# 06_-_SAMA7D65-DDR3L.net
KiCad netlist of a schematic drawn in Altium Designer
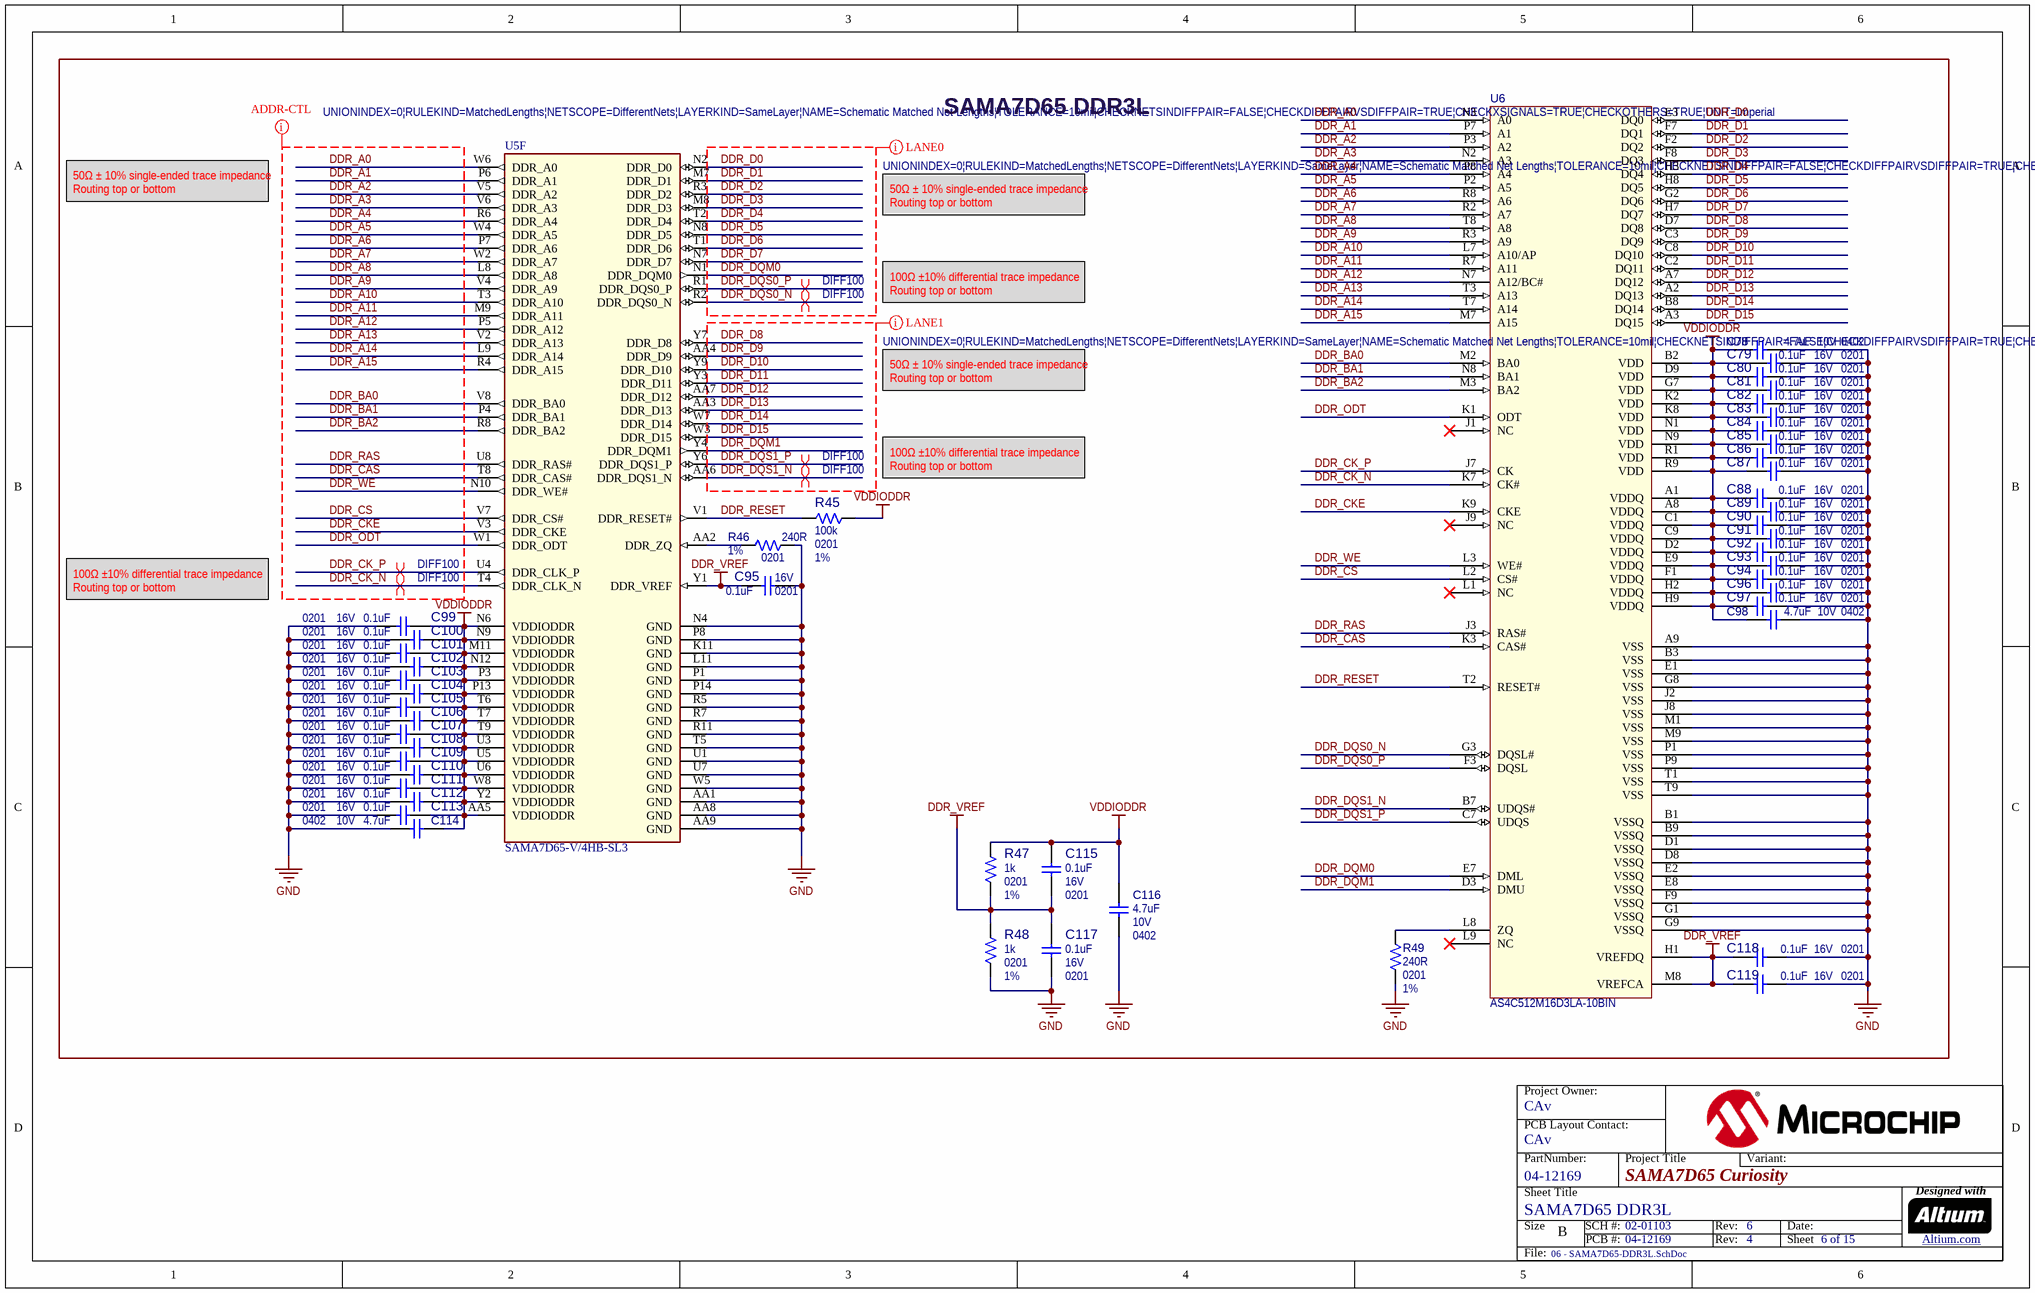
[diagram p0: 06 - SAMA7D65-DDR3L.SchDoc]

(export (version "E")
  (design (tool "Eeschema 10.0.6"))
  (components
    (comp (ref "C78")
      (value "4.7uF")
      (footprint "CAP_C_0402")
      (description "Capacitor")
      (fields
        (field (name "VOLTAGE") "10V")
        (field (name "PACKAGE") "0402")
        (field (name "TOLERANCE") "10%")
        (field (name "Comment") "Capacitor NP")
        (field (name "OWNER") "Jesus Aviles")
      )
      (libsource (lib "MCHP-CDB") (part "Capacitor NP"))
    )
    (comp (ref "C79")
      (value "0.1uF")
      (footprint "CAP_C_0201")
      (fields
        (field (name "VOLTAGE") "16V")
        (field (name "PACKAGE") "0201")
        (field (name "TOLERANCE") "10%")
        (field (name "Comment") "Capacitor NP")
        (field (name "OWNER") "Dragos Danaila")
      )
      (libsource (lib "") (part "Capacitor NP_1"))
    )
    (comp (ref "C80")
      (value "0.1uF")
      (footprint "CAP_C_0201")
      (fields
        (field (name "VOLTAGE") "16V")
        (field (name "PACKAGE") "0201")
        (field (name "TOLERANCE") "10%")
        (field (name "Comment") "Capacitor NP")
        (field (name "OWNER") "Dragos Danaila")
      )
      (libsource (lib "") (part "Capacitor NP_1"))
    )
    (comp (ref "C81")
      (value "0.1uF")
      (footprint "CAP_C_0201")
      (fields
        (field (name "VOLTAGE") "16V")
        (field (name "PACKAGE") "0201")
        (field (name "TOLERANCE") "10%")
        (field (name "Comment") "Capacitor NP")
        (field (name "OWNER") "Dragos Danaila")
      )
      (libsource (lib "") (part "Capacitor NP_1"))
    )
    (comp (ref "C82")
      (value "0.1uF")
      (footprint "CAP_C_0201")
      (fields
        (field (name "VOLTAGE") "16V")
        (field (name "PACKAGE") "0201")
        (field (name "TOLERANCE") "10%")
        (field (name "Comment") "Capacitor NP")
        (field (name "OWNER") "Dragos Danaila")
      )
      (libsource (lib "") (part "Capacitor NP_1"))
    )
    (comp (ref "C83")
      (value "0.1uF")
      (footprint "CAP_C_0201")
      (fields
        (field (name "VOLTAGE") "16V")
        (field (name "PACKAGE") "0201")
        (field (name "TOLERANCE") "10%")
        (field (name "Comment") "Capacitor NP")
        (field (name "OWNER") "Dragos Danaila")
      )
      (libsource (lib "") (part "Capacitor NP_1"))
    )
    (comp (ref "C84")
      (value "0.1uF")
      (footprint "CAP_C_0201")
      (fields
        (field (name "VOLTAGE") "16V")
        (field (name "PACKAGE") "0201")
        (field (name "TOLERANCE") "10%")
        (field (name "Comment") "Capacitor NP")
        (field (name "OWNER") "Dragos Danaila")
      )
      (libsource (lib "") (part "Capacitor NP_1"))
    )
    (comp (ref "C85")
      (value "0.1uF")
      (footprint "CAP_C_0201")
      (fields
        (field (name "VOLTAGE") "16V")
        (field (name "PACKAGE") "0201")
        (field (name "TOLERANCE") "10%")
        (field (name "Comment") "Capacitor NP")
        (field (name "OWNER") "Dragos Danaila")
      )
      (libsource (lib "") (part "Capacitor NP_1"))
    )
    (comp (ref "C86")
      (value "0.1uF")
      (footprint "CAP_C_0201")
      (fields
        (field (name "VOLTAGE") "16V")
        (field (name "PACKAGE") "0201")
        (field (name "TOLERANCE") "10%")
        (field (name "Comment") "Capacitor NP")
        (field (name "OWNER") "Dragos Danaila")
      )
      (libsource (lib "") (part "Capacitor NP_1"))
    )
    (comp (ref "C87")
      (value "0.1uF")
      (footprint "CAP_C_0201")
      (fields
        (field (name "VOLTAGE") "16V")
        (field (name "PACKAGE") "0201")
        (field (name "TOLERANCE") "10%")
        (field (name "Comment") "Capacitor NP")
        (field (name "OWNER") "Dragos Danaila")
      )
      (libsource (lib "") (part "Capacitor NP_1"))
    )
    (comp (ref "C88")
      (value "0.1uF")
      (footprint "CAP_C_0201")
      (fields
        (field (name "VOLTAGE") "16V")
        (field (name "PACKAGE") "0201")
        (field (name "TOLERANCE") "10%")
        (field (name "Comment") "Capacitor NP")
        (field (name "OWNER") "Dragos Danaila")
      )
      (libsource (lib "") (part "Capacitor NP_1"))
    )
    (comp (ref "C89")
      (value "0.1uF")
      (footprint "CAP_C_0201")
      (fields
        (field (name "VOLTAGE") "16V")
        (field (name "PACKAGE") "0201")
        (field (name "TOLERANCE") "10%")
        (field (name "Comment") "Capacitor NP")
        (field (name "OWNER") "Dragos Danaila")
      )
      (libsource (lib "") (part "Capacitor NP_1"))
    )
    (comp (ref "C90")
      (value "0.1uF")
      (footprint "CAP_C_0201")
      (fields
        (field (name "VOLTAGE") "16V")
        (field (name "PACKAGE") "0201")
        (field (name "TOLERANCE") "10%")
        (field (name "Comment") "Capacitor NP")
        (field (name "OWNER") "Dragos Danaila")
      )
      (libsource (lib "") (part "Capacitor NP_1"))
    )
    (comp (ref "C91")
      (value "0.1uF")
      (footprint "CAP_C_0201")
      (fields
        (field (name "VOLTAGE") "16V")
        (field (name "PACKAGE") "0201")
        (field (name "TOLERANCE") "10%")
        (field (name "Comment") "Capacitor NP")
        (field (name "OWNER") "Dragos Danaila")
      )
      (libsource (lib "") (part "Capacitor NP_1"))
    )
    (comp (ref "C92")
      (value "0.1uF")
      (footprint "CAP_C_0201")
      (fields
        (field (name "VOLTAGE") "16V")
        (field (name "PACKAGE") "0201")
        (field (name "TOLERANCE") "10%")
        (field (name "Comment") "Capacitor NP")
        (field (name "OWNER") "Dragos Danaila")
      )
      (libsource (lib "") (part "Capacitor NP_1"))
    )
    (comp (ref "C93")
      (value "0.1uF")
      (footprint "CAP_C_0201")
      (fields
        (field (name "VOLTAGE") "16V")
        (field (name "PACKAGE") "0201")
        (field (name "TOLERANCE") "10%")
        (field (name "Comment") "Capacitor NP")
        (field (name "OWNER") "Dragos Danaila")
      )
      (libsource (lib "") (part "Capacitor NP_1"))
    )
    (comp (ref "C94")
      (value "0.1uF")
      (footprint "CAP_C_0201")
      (fields
        (field (name "VOLTAGE") "16V")
        (field (name "PACKAGE") "0201")
        (field (name "TOLERANCE") "10%")
        (field (name "Comment") "Capacitor NP")
        (field (name "OWNER") "Dragos Danaila")
      )
      (libsource (lib "") (part "Capacitor NP_1"))
    )
    (comp (ref "C95")
      (value "0.1uF")
      (footprint "CAP_C_0201")
      (fields
        (field (name "VOLTAGE") "16V")
        (field (name "PACKAGE") "0201")
        (field (name "TOLERANCE") "10%")
        (field (name "Comment") "Capacitor NP")
        (field (name "OWNER") "Dragos Danaila")
      )
      (libsource (lib "") (part "Capacitor NP_1"))
    )
    (comp (ref "C96")
      (value "0.1uF")
      (footprint "CAP_C_0201")
      (fields
        (field (name "VOLTAGE") "16V")
        (field (name "PACKAGE") "0201")
        (field (name "TOLERANCE") "10%")
        (field (name "Comment") "Capacitor NP")
        (field (name "OWNER") "Dragos Danaila")
      )
      (libsource (lib "") (part "Capacitor NP_1"))
    )
    (comp (ref "C97")
      (value "0.1uF")
      (footprint "CAP_C_0201")
      (fields
        (field (name "VOLTAGE") "16V")
        (field (name "PACKAGE") "0201")
        (field (name "TOLERANCE") "10%")
        (field (name "Comment") "Capacitor NP")
        (field (name "OWNER") "Dragos Danaila")
      )
      (libsource (lib "") (part "Capacitor NP_1"))
    )
    (comp (ref "C98")
      (value "4.7uF")
      (footprint "CAP_C_0402")
      (description "Capacitor")
      (fields
        (field (name "VOLTAGE") "10V")
        (field (name "PACKAGE") "0402")
        (field (name "TOLERANCE") "10%")
        (field (name "Comment") "Capacitor NP")
        (field (name "OWNER") "Jesus Aviles")
      )
      (libsource (lib "MCHP-CDB") (part "Capacitor NP"))
    )
    (comp (ref "C99")
      (value "0.1uF")
      (footprint "CAP_C_0201")
      (fields
        (field (name "VOLTAGE") "16V")
        (field (name "PACKAGE") "0201")
        (field (name "TOLERANCE") "10%")
        (field (name "Comment") "Capacitor NP")
        (field (name "OWNER") "Dragos Danaila")
      )
      (libsource (lib "") (part "Capacitor NP_1"))
    )
    (comp (ref "C100")
      (value "0.1uF")
      (footprint "CAP_C_0201")
      (fields
        (field (name "VOLTAGE") "16V")
        (field (name "PACKAGE") "0201")
        (field (name "TOLERANCE") "10%")
        (field (name "Comment") "Capacitor NP")
        (field (name "OWNER") "Dragos Danaila")
      )
      (libsource (lib "") (part "Capacitor NP_1"))
    )
    (comp (ref "C101")
      (value "0.1uF")
      (footprint "CAP_C_0201")
      (fields
        (field (name "VOLTAGE") "16V")
        (field (name "PACKAGE") "0201")
        (field (name "TOLERANCE") "10%")
        (field (name "Comment") "Capacitor NP")
        (field (name "OWNER") "Dragos Danaila")
      )
      (libsource (lib "") (part "Capacitor NP_1"))
    )
    (comp (ref "C102")
      (value "0.1uF")
      (footprint "CAP_C_0201")
      (fields
        (field (name "VOLTAGE") "16V")
        (field (name "PACKAGE") "0201")
        (field (name "TOLERANCE") "10%")
        (field (name "Comment") "Capacitor NP")
        (field (name "OWNER") "Dragos Danaila")
      )
      (libsource (lib "") (part "Capacitor NP_1"))
    )
    (comp (ref "C103")
      (value "0.1uF")
      (footprint "CAP_C_0201")
      (fields
        (field (name "VOLTAGE") "16V")
        (field (name "PACKAGE") "0201")
        (field (name "TOLERANCE") "10%")
        (field (name "Comment") "Capacitor NP")
        (field (name "OWNER") "Dragos Danaila")
      )
      (libsource (lib "") (part "Capacitor NP_1"))
    )
    (comp (ref "C104")
      (value "0.1uF")
      (footprint "CAP_C_0201")
      (fields
        (field (name "VOLTAGE") "16V")
        (field (name "PACKAGE") "0201")
        (field (name "TOLERANCE") "10%")
        (field (name "Comment") "Capacitor NP")
        (field (name "OWNER") "Dragos Danaila")
      )
      (libsource (lib "") (part "Capacitor NP_1"))
    )
    (comp (ref "C105")
      (value "0.1uF")
      (footprint "CAP_C_0201")
      (fields
        (field (name "VOLTAGE") "16V")
        (field (name "PACKAGE") "0201")
        (field (name "TOLERANCE") "10%")
        (field (name "Comment") "Capacitor NP")
        (field (name "OWNER") "Dragos Danaila")
      )
      (libsource (lib "") (part "Capacitor NP_1"))
    )
    (comp (ref "C106")
      (value "0.1uF")
      (footprint "CAP_C_0201")
      (fields
        (field (name "VOLTAGE") "16V")
        (field (name "PACKAGE") "0201")
        (field (name "TOLERANCE") "10%")
        (field (name "Comment") "Capacitor NP")
        (field (name "OWNER") "Dragos Danaila")
      )
      (libsource (lib "") (part "Capacitor NP_1"))
    )
    (comp (ref "C107")
      (value "0.1uF")
      (footprint "CAP_C_0201")
      (fields
        (field (name "VOLTAGE") "16V")
        (field (name "PACKAGE") "0201")
        (field (name "TOLERANCE") "10%")
        (field (name "Comment") "Capacitor NP")
        (field (name "OWNER") "Dragos Danaila")
      )
      (libsource (lib "") (part "Capacitor NP_1"))
    )
    (comp (ref "C108")
      (value "0.1uF")
      (footprint "CAP_C_0201")
      (fields
        (field (name "VOLTAGE") "16V")
        (field (name "PACKAGE") "0201")
        (field (name "TOLERANCE") "10%")
        (field (name "Comment") "Capacitor NP")
        (field (name "OWNER") "Dragos Danaila")
      )
      (libsource (lib "") (part "Capacitor NP_1"))
    )
    (comp (ref "C109")
      (value "0.1uF")
      (footprint "CAP_C_0201")
      (fields
        (field (name "VOLTAGE") "16V")
        (field (name "PACKAGE") "0201")
        (field (name "TOLERANCE") "10%")
        (field (name "Comment") "Capacitor NP")
        (field (name "OWNER") "Dragos Danaila")
      )
      (libsource (lib "") (part "Capacitor NP_1"))
    )
    (comp (ref "C110")
      (value "0.1uF")
      (footprint "CAP_C_0201")
      (fields
        (field (name "VOLTAGE") "16V")
        (field (name "PACKAGE") "0201")
        (field (name "TOLERANCE") "10%")
        (field (name "Comment") "Capacitor NP")
        (field (name "OWNER") "Dragos Danaila")
      )
      (libsource (lib "") (part "Capacitor NP_1"))
    )
    (comp (ref "C111")
      (value "0.1uF")
      (footprint "CAP_C_0201")
      (fields
        (field (name "VOLTAGE") "16V")
        (field (name "PACKAGE") "0201")
        (field (name "TOLERANCE") "10%")
        (field (name "Comment") "Capacitor NP")
        (field (name "OWNER") "Dragos Danaila")
      )
      (libsource (lib "") (part "Capacitor NP_1"))
    )
    (comp (ref "C112")
      (value "0.1uF")
      (footprint "CAP_C_0201")
      (fields
        (field (name "VOLTAGE") "16V")
        (field (name "PACKAGE") "0201")
        (field (name "TOLERANCE") "10%")
        (field (name "Comment") "Capacitor NP")
        (field (name "OWNER") "Dragos Danaila")
      )
      (libsource (lib "") (part "Capacitor NP_1"))
    )
    (comp (ref "C113")
      (value "0.1uF")
      (footprint "CAP_C_0201")
      (fields
        (field (name "VOLTAGE") "16V")
        (field (name "PACKAGE") "0201")
        (field (name "TOLERANCE") "10%")
        (field (name "Comment") "Capacitor NP")
        (field (name "OWNER") "Dragos Danaila")
      )
      (libsource (lib "") (part "Capacitor NP_1"))
    )
    (comp (ref "C114")
      (value "4.7uF")
      (footprint "CAP_C_0402")
      (description "Capacitor")
      (fields
        (field (name "VOLTAGE") "10V")
        (field (name "PACKAGE") "0402")
        (field (name "TOLERANCE") "10%")
        (field (name "Comment") "Capacitor NP")
        (field (name "OWNER") "Jesus Aviles")
      )
      (libsource (lib "MCHP-CDB") (part "Capacitor NP"))
    )
    (comp (ref "C115")
      (value "0.1uF")
      (footprint "CAP_C_0201")
      (fields
        (field (name "VOLTAGE") "16V")
        (field (name "PACKAGE") "0201")
        (field (name "TOLERANCE") "10%")
        (field (name "Comment") "Capacitor NP")
        (field (name "OWNER") "Dragos Danaila")
      )
      (libsource (lib "") (part "Capacitor NP_1"))
    )
    (comp (ref "C116")
      (value "4.7uF")
      (footprint "CAP_C_0402")
      (description "Capacitor")
      (fields
        (field (name "VOLTAGE") "10V")
        (field (name "PACKAGE") "0402")
        (field (name "TOLERANCE") "10%")
        (field (name "Comment") "Capacitor NP")
        (field (name "OWNER") "Jesus Aviles")
      )
      (libsource (lib "MCHP-CDB") (part "Capacitor NP"))
    )
    (comp (ref "C117")
      (value "0.1uF")
      (footprint "CAP_C_0201")
      (fields
        (field (name "VOLTAGE") "16V")
        (field (name "PACKAGE") "0201")
        (field (name "TOLERANCE") "10%")
        (field (name "Comment") "Capacitor NP")
        (field (name "OWNER") "Dragos Danaila")
      )
      (libsource (lib "") (part "Capacitor NP_1"))
    )
    (comp (ref "C118")
      (value "0.1uF")
      (footprint "CAP_C_0201")
      (fields
        (field (name "VOLTAGE") "16V")
        (field (name "PACKAGE") "0201")
        (field (name "TOLERANCE") "10%")
        (field (name "Comment") "Capacitor NP")
        (field (name "OWNER") "Dragos Danaila")
      )
      (libsource (lib "") (part "Capacitor NP_1"))
    )
    (comp (ref "C119")
      (value "0.1uF")
      (footprint "CAP_C_0201")
      (fields
        (field (name "VOLTAGE") "16V")
        (field (name "PACKAGE") "0201")
        (field (name "TOLERANCE") "10%")
        (field (name "Comment") "Capacitor NP")
        (field (name "OWNER") "Dragos Danaila")
      )
      (libsource (lib "") (part "Capacitor NP_1"))
    )
    (comp (ref "R45")
      (value "100k")
      (footprint "RES_C_0201")
      (description "Resistor")
      (fields
        (field (name "PACKAGE") "0201")
        (field (name "TOLERANCE") "1%")
        (field (name "VOLTAGE") "25V")
        (field (name "POWER") "1/20W")
        (field (name "OWNER") "Ciprian Abramov")
      )
      (libsource (lib "") (part "Resistor_1"))
    )
    (comp (ref "R46")
      (value "240R")
      (footprint "RES_C_0201")
      (description "Resistor")
      (fields
        (field (name "PACKAGE") "0201")
        (field (name "TOLERANCE") "1%")
        (field (name "VOLTAGE") "25V")
        (field (name "POWER") "1/20W")
        (field (name "OWNER") "Dragos Danaila")
      )
      (libsource (lib "MCHP-CDB") (part "Resistor"))
    )
    (comp (ref "R47")
      (value "1k")
      (footprint "RES_C_0201")
      (description "Resistor")
      (fields
        (field (name "PACKAGE") "0201")
        (field (name "TOLERANCE") "1%")
        (field (name "VOLTAGE") "25V")
        (field (name "POWER") "1/20W")
        (field (name "OWNER") "Gabor Bihari")
      )
      (libsource (lib "") (part "Resistor_1"))
    )
    (comp (ref "R48")
      (value "1k")
      (footprint "RES_C_0201")
      (description "Resistor")
      (fields
        (field (name "PACKAGE") "0201")
        (field (name "TOLERANCE") "1%")
        (field (name "VOLTAGE") "25V")
        (field (name "POWER") "1/20W")
        (field (name "OWNER") "Gabor Bihari")
      )
      (libsource (lib "") (part "Resistor_1"))
    )
    (comp (ref "R49")
      (value "240R")
      (footprint "RES_C_0201")
      (description "Resistor")
      (fields
        (field (name "PACKAGE") "0201")
        (field (name "TOLERANCE") "1%")
        (field (name "VOLTAGE") "25V")
        (field (name "POWER") "1/20W")
        (field (name "OWNER") "Dragos Danaila")
      )
      (libsource (lib "MCHP-CDB") (part "Resistor"))
    )
    (comp (ref "U5")
      (value "SAMA7D65-V/4HB-SL3")
      (footprint "TFBGA-343_14x14")
      (description "SAMA7D65 MPU 1000MHz Cortex-A7 TFBGA-343")
      (fields (field (name "Comment") "SAMA7D65") (field (name "OWNER") "Ciprian Abramov"))
      (libsource (lib "MCHP-CDB") (part "SAMA7D65-TFBGA-343"))
    )
    (comp (ref "U6")
      (value "AS4C512M16D3LA-10BIN")
      (footprint "TFBGA-96_13.5x9")
      (description "8Gb DDR3L-1866 SDRAM, 512Mb x 16, -40C to +95C")
      (fields
        (field (name "Comment") "AS4C512M16D3LA-10BIN TFBGA-96")
        (field (name "OWNER") "Ciprian Abramov")
      )
      (libsource (lib "MCHP-CDB") (part "AS4C512M16D3LA-10BIN TFBGA-96"))
    )
  )
  (nets
    (net (code "1") (name "/DDR_A0") (class "Default")
      (node (ref "U5") (pin "W6") (pinfunction "DDR_A0_W6") (pintype "output"))
      (node (ref "U6") (pin "N3") (pinfunction "A0_N3") (pintype "input"))
    )
    (net (code "2") (name "/DDR_A1") (class "Default")
      (node (ref "U5") (pin "P6") (pinfunction "DDR_A1_P6") (pintype "output"))
      (node (ref "U6") (pin "P7") (pinfunction "A1_P7") (pintype "input"))
    )
    (net (code "3") (name "/DDR_A2") (class "Default")
      (node (ref "U5") (pin "V5") (pinfunction "DDR_A2_V5") (pintype "output"))
      (node (ref "U6") (pin "P3") (pinfunction "A2_P3") (pintype "input"))
    )
    (net (code "4") (name "/DDR_A3") (class "Default")
      (node (ref "U5") (pin "V6") (pinfunction "DDR_A3_V6") (pintype "output"))
      (node (ref "U6") (pin "N2") (pinfunction "A3_N2") (pintype "input"))
    )
    (net (code "5") (name "/DDR_A4") (class "Default")
      (node (ref "U5") (pin "R6") (pinfunction "DDR_A4_R6") (pintype "output"))
      (node (ref "U6") (pin "P8") (pinfunction "A4_P8") (pintype "input"))
    )
    (net (code "6") (name "/DDR_A5") (class "Default")
      (node (ref "U5") (pin "W4") (pinfunction "DDR_A5_W4") (pintype "output"))
      (node (ref "U6") (pin "P2") (pinfunction "A5_P2") (pintype "input"))
    )
    (net (code "7") (name "/DDR_A6") (class "Default")
      (node (ref "U5") (pin "P7") (pinfunction "DDR_A6_P7") (pintype "output"))
      (node (ref "U6") (pin "R8") (pinfunction "A6_R8") (pintype "input"))
    )
    (net (code "8") (name "/DDR_A7") (class "Default")
      (node (ref "U5") (pin "W2") (pinfunction "DDR_A7_W2") (pintype "output"))
      (node (ref "U6") (pin "R2") (pinfunction "A7_R2") (pintype "input"))
    )
    (net (code "9") (name "/DDR_A8") (class "Default")
      (node (ref "U5") (pin "L8") (pinfunction "DDR_A8_L8") (pintype "output"))
      (node (ref "U6") (pin "T8") (pinfunction "A8_T8") (pintype "input"))
    )
    (net (code "10") (name "/DDR_A9") (class "Default")
      (node (ref "U5") (pin "V4") (pinfunction "DDR_A9_V4") (pintype "output"))
      (node (ref "U6") (pin "R3") (pinfunction "A9_R3") (pintype "input"))
    )
    (net (code "11") (name "/DDR_A10") (class "Default")
      (node (ref "U5") (pin "T3") (pinfunction "DDR_A10_T3") (pintype "output"))
      (node (ref "U6") (pin "L7") (pinfunction "A10/AP_L7") (pintype "input"))
    )
    (net (code "12") (name "/DDR_A11") (class "Default")
      (node (ref "U5") (pin "M9") (pinfunction "DDR_A11_M9") (pintype "output"))
      (node (ref "U6") (pin "R7") (pinfunction "A11_R7") (pintype "input"))
    )
    (net (code "13") (name "/DDR_A12") (class "Default")
      (node (ref "U5") (pin "P5") (pinfunction "DDR_A12_P5") (pintype "output"))
      (node (ref "U6") (pin "N7") (pinfunction "A12/BC#_N7") (pintype "passive"))
    )
    (net (code "14") (name "/DDR_A13") (class "Default")
      (node (ref "U5") (pin "V2") (pinfunction "DDR_A13_V2") (pintype "output"))
      (node (ref "U6") (pin "T3") (pinfunction "A13_T3") (pintype "input"))
    )
    (net (code "15") (name "/DDR_A14") (class "Default")
      (node (ref "U5") (pin "L9") (pinfunction "DDR_A14_L9") (pintype "output"))
      (node (ref "U6") (pin "T7") (pinfunction "A14_T7") (pintype "input"))
    )
    (net (code "16") (name "/DDR_A15") (class "Default")
      (node (ref "U5") (pin "R4") (pinfunction "DDR_A15_R4") (pintype "output"))
      (node (ref "U6") (pin "M7") (pinfunction "A15_M7") (pintype "passive"))
    )
    (net (code "17") (name "/DDR_BA0") (class "Default")
      (node (ref "U5") (pin "V8") (pinfunction "DDR_BA0_V8") (pintype "output"))
      (node (ref "U6") (pin "M2") (pinfunction "BA0_M2") (pintype "input"))
    )
    (net (code "18") (name "/DDR_BA1") (class "Default")
      (node (ref "U5") (pin "P4") (pinfunction "DDR_BA1_P4") (pintype "output"))
      (node (ref "U6") (pin "N8") (pinfunction "BA1_N8") (pintype "input"))
    )
    (net (code "19") (name "/DDR_BA2") (class "Default")
      (node (ref "U5") (pin "R8") (pinfunction "DDR_BA2_R8") (pintype "output"))
      (node (ref "U6") (pin "M3") (pinfunction "BA2_M3") (pintype "input"))
    )
    (net (code "20") (name "/DDR_CAS") (class "Default")
      (node (ref "U5") (pin "T8") (pinfunction "DDR_CAS#_T8") (pintype "output"))
      (node (ref "U6") (pin "K3") (pinfunction "CAS#_K3") (pintype "input"))
    )
    (net (code "21") (name "/DDR_CKE") (class "Default")
      (node (ref "U5") (pin "V3") (pinfunction "DDR_CKE_V3") (pintype "output"))
      (node (ref "U6") (pin "K9") (pinfunction "CKE_K9") (pintype "input"))
    )
    (net (code "22") (name "/DDR_CK_N") (class "Default")
      (node (ref "U5") (pin "T4") (pinfunction "DDR_CLK_N_T4") (pintype "output"))
      (node (ref "U6") (pin "K7") (pinfunction "CK#_K7") (pintype "input"))
    )
    (net (code "23") (name "/DDR_CK_P") (class "Default")
      (node (ref "U5") (pin "U4") (pinfunction "DDR_CLK_P_U4") (pintype "output"))
      (node (ref "U6") (pin "J7") (pinfunction "CK_J7") (pintype "input"))
    )
    (net (code "24") (name "/DDR_CS") (class "Default")
      (node (ref "U5") (pin "V7") (pinfunction "DDR_CS#_V7") (pintype "output"))
      (node (ref "U6") (pin "L2") (pinfunction "CS#_L2") (pintype "input"))
    )
    (net (code "25") (name "/DDR_D0") (class "Default")
      (node (ref "U5") (pin "N2") (pinfunction "DDR_D0_N2") (pintype "bidirectional"))
      (node (ref "U6") (pin "E3") (pinfunction "DQ0_E3") (pintype "bidirectional"))
    )
    (net (code "26") (name "/DDR_D1") (class "Default")
      (node (ref "U5") (pin "M7") (pinfunction "DDR_D1_M7") (pintype "bidirectional"))
      (node (ref "U6") (pin "F7") (pinfunction "DQ1_F7") (pintype "bidirectional"))
    )
    (net (code "27") (name "/DDR_D2") (class "Default")
      (node (ref "U5") (pin "R3") (pinfunction "DDR_D2_R3") (pintype "bidirectional"))
      (node (ref "U6") (pin "F2") (pinfunction "DQ2_F2") (pintype "bidirectional"))
    )
    (net (code "28") (name "/DDR_D3") (class "Default")
      (node (ref "U5") (pin "M8") (pinfunction "DDR_D3_M8") (pintype "bidirectional"))
      (node (ref "U6") (pin "F8") (pinfunction "DQ3_F8") (pintype "bidirectional"))
    )
    (net (code "29") (name "/DDR_D4") (class "Default")
      (node (ref "U5") (pin "T2") (pinfunction "DDR_D4_T2") (pintype "bidirectional"))
      (node (ref "U6") (pin "H3") (pinfunction "DQ4_H3") (pintype "bidirectional"))
    )
    (net (code "30") (name "/DDR_D5") (class "Default")
      (node (ref "U5") (pin "N8") (pinfunction "DDR_D5_N8") (pintype "bidirectional"))
      (node (ref "U6") (pin "H8") (pinfunction "DQ5_H8") (pintype "bidirectional"))
    )
    (net (code "31") (name "/DDR_D6") (class "Default")
      (node (ref "U5") (pin "T1") (pinfunction "DDR_D6_T1") (pintype "bidirectional"))
      (node (ref "U6") (pin "G2") (pinfunction "DQ6_G2") (pintype "bidirectional"))
    )
    (net (code "32") (name "/DDR_D7") (class "Default")
      (node (ref "U5") (pin "N7") (pinfunction "DDR_D7_N7") (pintype "bidirectional"))
      (node (ref "U6") (pin "H7") (pinfunction "DQ7_H7") (pintype "bidirectional"))
    )
    (net (code "33") (name "/DDR_D8") (class "Default")
      (node (ref "U5") (pin "Y7") (pinfunction "DDR_D8_Y7") (pintype "bidirectional"))
      (node (ref "U6") (pin "D7") (pinfunction "DQ8_D7") (pintype "bidirectional"))
    )
    (net (code "34") (name "/DDR_D9") (class "Default")
      (node (ref "U5") (pin "AA4") (pinfunction "DDR_D9_AA4") (pintype "bidirectional"))
      (node (ref "U6") (pin "C3") (pinfunction "DQ9_C3") (pintype "bidirectional"))
    )
    (net (code "35") (name "/DDR_D10") (class "Default")
      (node (ref "U5") (pin "Y9") (pinfunction "DDR_D10_Y9") (pintype "bidirectional"))
      (node (ref "U6") (pin "C8") (pinfunction "DQ10_C8") (pintype "bidirectional"))
    )
    (net (code "36") (name "/DDR_D11") (class "Default")
      (node (ref "U5") (pin "Y3") (pinfunction "DDR_D11_Y3") (pintype "bidirectional"))
      (node (ref "U6") (pin "C2") (pinfunction "DQ11_C2") (pintype "bidirectional"))
    )
    (net (code "37") (name "/DDR_D12") (class "Default")
      (node (ref "U5") (pin "AA7") (pinfunction "DDR_D12_AA7") (pintype "bidirectional"))
      (node (ref "U6") (pin "A7") (pinfunction "DQ12_A7") (pintype "bidirectional"))
    )
    (net (code "38") (name "/DDR_D13") (class "Default")
      (node (ref "U5") (pin "AA3") (pinfunction "DDR_D13_AA3") (pintype "bidirectional"))
      (node (ref "U6") (pin "A2") (pinfunction "DQ13_A2") (pintype "bidirectional"))
    )
    (net (code "39") (name "/DDR_D14") (class "Default")
      (node (ref "U5") (pin "W7") (pinfunction "DDR_D14_W7") (pintype "bidirectional"))
      (node (ref "U6") (pin "B8") (pinfunction "DQ14_B8") (pintype "bidirectional"))
    )
    (net (code "40") (name "/DDR_D15") (class "Default")
      (node (ref "U5") (pin "W3") (pinfunction "DDR_D15_W3") (pintype "bidirectional"))
      (node (ref "U6") (pin "A3") (pinfunction "DQ15_A3") (pintype "bidirectional"))
    )
    (net (code "41") (name "/DDR_DQM0") (class "Default")
      (node (ref "U5") (pin "N1") (pinfunction "DDR_DQM0_N1") (pintype "output"))
      (node (ref "U6") (pin "E7") (pinfunction "DML_E7") (pintype "input"))
    )
    (net (code "42") (name "/DDR_DQM1") (class "Default")
      (node (ref "U5") (pin "Y4") (pinfunction "DDR_DQM1_Y4") (pintype "output"))
      (node (ref "U6") (pin "D3") (pinfunction "DMU_D3") (pintype "input"))
    )
    (net (code "43") (name "/DDR_DQS0_N") (class "Default")
      (node (ref "U5") (pin "R2") (pinfunction "DDR_DQS0_N_R2") (pintype "bidirectional"))
      (node (ref "U6") (pin "G3") (pinfunction "DQSL#_G3") (pintype "bidirectional"))
    )
    (net (code "44") (name "/DDR_DQS0_P") (class "Default")
      (node (ref "U5") (pin "R1") (pinfunction "DDR_DQS0_P_R1") (pintype "bidirectional"))
      (node (ref "U6") (pin "F3") (pinfunction "DQSL_F3") (pintype "bidirectional"))
    )
    (net (code "45") (name "/DDR_DQS1_N") (class "Default")
      (node (ref "U5") (pin "AA6") (pinfunction "DDR_DQS1_N_AA6") (pintype "bidirectional"))
      (node (ref "U6") (pin "B7") (pinfunction "UDQS#_B7") (pintype "bidirectional"))
    )
    (net (code "46") (name "/DDR_DQS1_P") (class "Default")
      (node (ref "U5") (pin "Y6") (pinfunction "DDR_DQS1_P_Y6") (pintype "bidirectional"))
      (node (ref "U6") (pin "C7") (pinfunction "UDQS_C7") (pintype "bidirectional"))
    )
    (net (code "47") (name "/DDR_ODT") (class "Default")
      (node (ref "U5") (pin "W1") (pinfunction "DDR_ODT_W1") (pintype "output"))
      (node (ref "U6") (pin "K1") (pinfunction "ODT_K1") (pintype "input"))
    )
    (net (code "48") (name "/DDR_RAS") (class "Default")
      (node (ref "U5") (pin "U8") (pinfunction "DDR_RAS#_U8") (pintype "output"))
      (node (ref "U6") (pin "J3") (pinfunction "RAS#_J3") (pintype "input"))
    )
    (net (code "49") (name "/DDR_RESET") (class "Default")
      (node (ref "R45") (pin "1") (pinfunction "1_1") (pintype "passive"))
      (node (ref "U5") (pin "V1") (pinfunction "DDR_RESET#_V1") (pintype "output"))
      (node (ref "U6") (pin "T2") (pinfunction "RESET#_T2") (pintype "input"))
    )
    (net (code "50") (name "/DDR_WE") (class "Default")
      (node (ref "U5") (pin "N10") (pinfunction "DDR_WE#_N10") (pintype "output"))
      (node (ref "U6") (pin "L3") (pinfunction "WE#_L3") (pintype "input"))
    )
    (net (code "51") (name "DDR_VREF") (class "Default")
      (node (ref "C115") (pin "2") (pinfunction "2_2") (pintype "passive"))
      (node (ref "C117") (pin "1") (pinfunction "1_1") (pintype "passive"))
      (node (ref "C118") (pin "1") (pinfunction "1_1") (pintype "passive"))
      (node (ref "C119") (pin "1") (pinfunction "1_1") (pintype "passive"))
      (node (ref "C95") (pin "1") (pinfunction "1_1") (pintype "passive"))
      (node (ref "R47") (pin "1") (pinfunction "1_1") (pintype "passive"))
      (node (ref "R48") (pin "2") (pinfunction "2_2") (pintype "passive"))
      (node (ref "U5") (pin "Y1") (pinfunction "DDR_VREF_Y1") (pintype "input"))
      (node (ref "U6") (pin "H1") (pinfunction "VREFDQ_H1") (pintype "power_in"))
      (node (ref "U6") (pin "M8") (pinfunction "VREFCA_M8") (pintype "power_in"))
    )
    (net (code "52") (name "GND") (class "Default")
      (node (ref "C100") (pin "2") (pinfunction "2_2") (pintype "passive"))
      (node (ref "C101") (pin "2") (pinfunction "2_2") (pintype "passive"))
      (node (ref "C102") (pin "2") (pinfunction "2_2") (pintype "passive"))
      (node (ref "C103") (pin "2") (pinfunction "2_2") (pintype "passive"))
      (node (ref "C104") (pin "2") (pinfunction "2_2") (pintype "passive"))
      (node (ref "C105") (pin "2") (pinfunction "2_2") (pintype "passive"))
      (node (ref "C106") (pin "2") (pinfunction "2_2") (pintype "passive"))
      (node (ref "C107") (pin "2") (pinfunction "2_2") (pintype "passive"))
      (node (ref "C108") (pin "2") (pinfunction "2_2") (pintype "passive"))
      (node (ref "C109") (pin "2") (pinfunction "2_2") (pintype "passive"))
      (node (ref "C110") (pin "2") (pinfunction "2_2") (pintype "passive"))
      (node (ref "C111") (pin "2") (pinfunction "2_2") (pintype "passive"))
      (node (ref "C112") (pin "2") (pinfunction "2_2") (pintype "passive"))
      (node (ref "C113") (pin "2") (pinfunction "2_2") (pintype "passive"))
      (node (ref "C114") (pin "2") (pinfunction "2_2") (pintype "passive"))
      (node (ref "C116") (pin "1") (pinfunction "1_1") (pintype "passive"))
      (node (ref "C117") (pin "2") (pinfunction "2_2") (pintype "passive"))
      (node (ref "C118") (pin "2") (pinfunction "2_2") (pintype "passive"))
      (node (ref "C119") (pin "2") (pinfunction "2_2") (pintype "passive"))
      (node (ref "C78") (pin "1") (pinfunction "1_1") (pintype "passive"))
      (node (ref "C79") (pin "2") (pinfunction "2_2") (pintype "passive"))
      (node (ref "C80") (pin "2") (pinfunction "2_2") (pintype "passive"))
      (node (ref "C81") (pin "2") (pinfunction "2_2") (pintype "passive"))
      (node (ref "C82") (pin "2") (pinfunction "2_2") (pintype "passive"))
      (node (ref "C83") (pin "2") (pinfunction "2_2") (pintype "passive"))
      (node (ref "C84") (pin "2") (pinfunction "2_2") (pintype "passive"))
      (node (ref "C85") (pin "2") (pinfunction "2_2") (pintype "passive"))
      (node (ref "C86") (pin "2") (pinfunction "2_2") (pintype "passive"))
      (node (ref "C87") (pin "2") (pinfunction "2_2") (pintype "passive"))
      (node (ref "C88") (pin "2") (pinfunction "2_2") (pintype "passive"))
      (node (ref "C89") (pin "2") (pinfunction "2_2") (pintype "passive"))
      (node (ref "C90") (pin "2") (pinfunction "2_2") (pintype "passive"))
      (node (ref "C91") (pin "2") (pinfunction "2_2") (pintype "passive"))
      (node (ref "C92") (pin "2") (pinfunction "2_2") (pintype "passive"))
      (node (ref "C93") (pin "2") (pinfunction "2_2") (pintype "passive"))
      (node (ref "C94") (pin "2") (pinfunction "2_2") (pintype "passive"))
      (node (ref "C95") (pin "2") (pinfunction "2_2") (pintype "passive"))
      (node (ref "C96") (pin "2") (pinfunction "2_2") (pintype "passive"))
      (node (ref "C97") (pin "2") (pinfunction "2_2") (pintype "passive"))
      (node (ref "C98") (pin "1") (pinfunction "1_1") (pintype "passive"))
      (node (ref "C99") (pin "2") (pinfunction "2_2") (pintype "passive"))
      (node (ref "R46") (pin "2") (pinfunction "2_2") (pintype "passive"))
      (node (ref "R48") (pin "1") (pinfunction "1_1") (pintype "passive"))
      (node (ref "R49") (pin "1") (pinfunction "1_1") (pintype "passive"))
      (node (ref "U5") (pin "AA1") (pinfunction "GND_AA1") (pintype "power_in"))
      (node (ref "U5") (pin "AA8") (pinfunction "GND_AA8") (pintype "power_in"))
      (node (ref "U5") (pin "AA9") (pinfunction "GND_AA9") (pintype "power_in"))
      (node (ref "U5") (pin "K11") (pinfunction "GND_K11") (pintype "power_in"))
      (node (ref "U5") (pin "L11") (pinfunction "GND_L11") (pintype "power_in"))
      (node (ref "U5") (pin "N4") (pinfunction "GND_N4") (pintype "power_in"))
      (node (ref "U5") (pin "P1") (pinfunction "GND_P1") (pintype "power_in"))
      (node (ref "U5") (pin "P14") (pinfunction "GND_P14") (pintype "power_in"))
      (node (ref "U5") (pin "P8") (pinfunction "GND_P8") (pintype "power_in"))
      (node (ref "U5") (pin "R11") (pinfunction "GND_R11") (pintype "power_in"))
      (node (ref "U5") (pin "R5") (pinfunction "GND_R5") (pintype "power_in"))
      (node (ref "U5") (pin "R7") (pinfunction "GND_R7") (pintype "power_in"))
      (node (ref "U5") (pin "T5") (pinfunction "GND_T5") (pintype "power_in"))
      (node (ref "U5") (pin "U1") (pinfunction "GND_U1") (pintype "power_in"))
      (node (ref "U5") (pin "U7") (pinfunction "GND_U7") (pintype "power_in"))
      (node (ref "U5") (pin "W5") (pinfunction "GND_W5") (pintype "power_in"))
      (node (ref "U6") (pin "A9") (pinfunction "VSS_A9") (pintype "power_in"))
      (node (ref "U6") (pin "B1") (pinfunction "VSSQ_B1") (pintype "power_in"))
      (node (ref "U6") (pin "B3") (pinfunction "VSS_B3") (pintype "power_in"))
      (node (ref "U6") (pin "B9") (pinfunction "VSSQ_B9") (pintype "power_in"))
      (node (ref "U6") (pin "D1") (pinfunction "VSSQ_D1") (pintype "power_in"))
      (node (ref "U6") (pin "D8") (pinfunction "VSSQ_D8") (pintype "power_in"))
      (node (ref "U6") (pin "E1") (pinfunction "VSS_E1") (pintype "power_in"))
      (node (ref "U6") (pin "E2") (pinfunction "VSSQ_E2") (pintype "power_in"))
      (node (ref "U6") (pin "E8") (pinfunction "VSSQ_E8") (pintype "power_in"))
      (node (ref "U6") (pin "F9") (pinfunction "VSSQ_F9") (pintype "power_in"))
      (node (ref "U6") (pin "G1") (pinfunction "VSSQ_G1") (pintype "power_in"))
      (node (ref "U6") (pin "G8") (pinfunction "VSS_G8") (pintype "power_in"))
      (node (ref "U6") (pin "G9") (pinfunction "VSSQ_G9") (pintype "power_in"))
      (node (ref "U6") (pin "J2") (pinfunction "VSS_J2") (pintype "power_in"))
      (node (ref "U6") (pin "J8") (pinfunction "VSS_J8") (pintype "power_in"))
      (node (ref "U6") (pin "M1") (pinfunction "VSS_M1") (pintype "passive"))
      (node (ref "U6") (pin "M9") (pinfunction "VSS_M9") (pintype "power_in"))
      (node (ref "U6") (pin "P1") (pinfunction "VSS_P1") (pintype "power_in"))
      (node (ref "U6") (pin "P9") (pinfunction "VSS_P9") (pintype "passive"))
      (node (ref "U6") (pin "T1") (pinfunction "VSS_T1") (pintype "power_in"))
      (node (ref "U6") (pin "T9") (pinfunction "VSS_T9") (pintype "power_in"))
    )
    (net (code "53") (name "Net-(U5F-DDR_ZQ)") (class "Default")
      (node (ref "R46") (pin "1") (pinfunction "1_1") (pintype "passive"))
      (node (ref "U5") (pin "AA2") (pinfunction "DDR_ZQ_AA2") (pintype "input"))
    )
    (net (code "54") (name "Net-(U6-ZQ)") (class "Default")
      (node (ref "R49") (pin "2") (pinfunction "2_2") (pintype "passive"))
      (node (ref "U6") (pin "L8") (pinfunction "ZQ_L8") (pintype "passive"))
    )
    (net (code "55") (name "VDDIODDR") (class "Default")
      (node (ref "C100") (pin "1") (pinfunction "1_1") (pintype "passive"))
      (node (ref "C101") (pin "1") (pinfunction "1_1") (pintype "passive"))
      (node (ref "C102") (pin "1") (pinfunction "1_1") (pintype "passive"))
      (node (ref "C103") (pin "1") (pinfunction "1_1") (pintype "passive"))
      (node (ref "C104") (pin "1") (pinfunction "1_1") (pintype "passive"))
      (node (ref "C105") (pin "1") (pinfunction "1_1") (pintype "passive"))
      (node (ref "C106") (pin "1") (pinfunction "1_1") (pintype "passive"))
      (node (ref "C107") (pin "1") (pinfunction "1_1") (pintype "passive"))
      (node (ref "C108") (pin "1") (pinfunction "1_1") (pintype "passive"))
      (node (ref "C109") (pin "1") (pinfunction "1_1") (pintype "passive"))
      (node (ref "C110") (pin "1") (pinfunction "1_1") (pintype "passive"))
      (node (ref "C111") (pin "1") (pinfunction "1_1") (pintype "passive"))
      (node (ref "C112") (pin "1") (pinfunction "1_1") (pintype "passive"))
      (node (ref "C113") (pin "1") (pinfunction "1_1") (pintype "passive"))
      (node (ref "C114") (pin "1") (pinfunction "1_1") (pintype "passive"))
      (node (ref "C115") (pin "1") (pinfunction "1_1") (pintype "passive"))
      (node (ref "C116") (pin "2") (pinfunction "2_2") (pintype "passive"))
      (node (ref "C78") (pin "2") (pinfunction "2_2") (pintype "passive"))
      (node (ref "C79") (pin "1") (pinfunction "1_1") (pintype "passive"))
      (node (ref "C80") (pin "1") (pinfunction "1_1") (pintype "passive"))
      (node (ref "C81") (pin "1") (pinfunction "1_1") (pintype "passive"))
      (node (ref "C82") (pin "1") (pinfunction "1_1") (pintype "passive"))
      (node (ref "C83") (pin "1") (pinfunction "1_1") (pintype "passive"))
      (node (ref "C84") (pin "1") (pinfunction "1_1") (pintype "passive"))
      (node (ref "C85") (pin "1") (pinfunction "1_1") (pintype "passive"))
      (node (ref "C86") (pin "1") (pinfunction "1_1") (pintype "passive"))
      (node (ref "C87") (pin "1") (pinfunction "1_1") (pintype "passive"))
      (node (ref "C88") (pin "1") (pinfunction "1_1") (pintype "passive"))
      (node (ref "C89") (pin "1") (pinfunction "1_1") (pintype "passive"))
      (node (ref "C90") (pin "1") (pinfunction "1_1") (pintype "passive"))
      (node (ref "C91") (pin "1") (pinfunction "1_1") (pintype "passive"))
      (node (ref "C92") (pin "1") (pinfunction "1_1") (pintype "passive"))
      (node (ref "C93") (pin "1") (pinfunction "1_1") (pintype "passive"))
      (node (ref "C94") (pin "1") (pinfunction "1_1") (pintype "passive"))
      (node (ref "C96") (pin "1") (pinfunction "1_1") (pintype "passive"))
      (node (ref "C97") (pin "1") (pinfunction "1_1") (pintype "passive"))
      (node (ref "C98") (pin "2") (pinfunction "2_2") (pintype "passive"))
      (node (ref "C99") (pin "1") (pinfunction "1_1") (pintype "passive"))
      (node (ref "R45") (pin "2") (pinfunction "2_2") (pintype "passive"))
      (node (ref "R47") (pin "2") (pinfunction "2_2") (pintype "passive"))
      (node (ref "U5") (pin "AA5") (pinfunction "VDDIODDR_AA5") (pintype "power_in"))
      (node (ref "U5") (pin "M11") (pinfunction "VDDIODDR_M11") (pintype "power_in"))
      (node (ref "U5") (pin "N12") (pinfunction "VDDIODDR_N12") (pintype "power_in"))
      (node (ref "U5") (pin "N6") (pinfunction "VDDIODDR_N6") (pintype "power_in"))
      (node (ref "U5") (pin "N9") (pinfunction "VDDIODDR_N9") (pintype "power_in"))
      (node (ref "U5") (pin "P13") (pinfunction "VDDIODDR_P13") (pintype "power_in"))
      (node (ref "U5") (pin "P3") (pinfunction "VDDIODDR_P3") (pintype "power_in"))
      (node (ref "U5") (pin "T6") (pinfunction "VDDIODDR_T6") (pintype "power_in"))
      (node (ref "U5") (pin "T7") (pinfunction "VDDIODDR_T7") (pintype "power_in"))
      (node (ref "U5") (pin "T9") (pinfunction "VDDIODDR_T9") (pintype "power_in"))
      (node (ref "U5") (pin "U3") (pinfunction "VDDIODDR_U3") (pintype "power_in"))
      (node (ref "U5") (pin "U5") (pinfunction "VDDIODDR_U5") (pintype "power_in"))
      (node (ref "U5") (pin "U6") (pinfunction "VDDIODDR_U6") (pintype "power_in"))
      (node (ref "U5") (pin "W8") (pinfunction "VDDIODDR_W8") (pintype "power_in"))
      (node (ref "U5") (pin "Y2") (pinfunction "VDDIODDR_Y2") (pintype "power_in"))
      (node (ref "U6") (pin "A1") (pinfunction "VDDQ_A1") (pintype "power_in"))
      (node (ref "U6") (pin "A8") (pinfunction "VDDQ_A8") (pintype "power_in"))
      (node (ref "U6") (pin "B2") (pinfunction "VDD_B2") (pintype "power_in"))
      (node (ref "U6") (pin "C1") (pinfunction "VDDQ_C1") (pintype "power_in"))
      (node (ref "U6") (pin "C9") (pinfunction "VDDQ_C9") (pintype "passive"))
      (node (ref "U6") (pin "D2") (pinfunction "VDDQ_D2") (pintype "power_in"))
      (node (ref "U6") (pin "D9") (pinfunction "VDD_D9") (pintype "power_in"))
      (node (ref "U6") (pin "E9") (pinfunction "VDDQ_E9") (pintype "power_in"))
      (node (ref "U6") (pin "F1") (pinfunction "VDDQ_F1") (pintype "power_in"))
      (node (ref "U6") (pin "G7") (pinfunction "VDD_G7") (pintype "power_in"))
      (node (ref "U6") (pin "H2") (pinfunction "VDDQ_H2") (pintype "power_in"))
      (node (ref "U6") (pin "H9") (pinfunction "VDDQ_H9") (pintype "power_in"))
      (node (ref "U6") (pin "K2") (pinfunction "VDD_K2") (pintype "power_in"))
      (node (ref "U6") (pin "K8") (pinfunction "VDD_K8") (pintype "power_in"))
      (node (ref "U6") (pin "N1") (pinfunction "VDD_N1") (pintype "power_in"))
      (node (ref "U6") (pin "N9") (pinfunction "VDD_N9") (pintype "power_in"))
      (node (ref "U6") (pin "R1") (pinfunction "VDD_R1") (pintype "power_in"))
      (node (ref "U6") (pin "R9") (pinfunction "VDD_R9") (pintype "power_in"))
    )
    (net (code "56") (name "unconnected-(U6-NC-PadJ1)") (class "Default")
      (node (ref "U6") (pin "J1") (pinfunction "NC_J1") (pintype "input+no_connect"))
    )
    (net (code "57") (name "unconnected-(U6-NC-PadJ9)") (class "Default")
      (node (ref "U6") (pin "J9") (pinfunction "NC_J9") (pintype "input+no_connect"))
    )
    (net (code "58") (name "unconnected-(U6-NC-PadL1)") (class "Default")
      (node (ref "U6") (pin "L1") (pinfunction "NC_L1") (pintype "input+no_connect"))
    )
    (net (code "59") (name "unconnected-(U6-NC-PadL9)") (class "Default")
      (node (ref "U6") (pin "L9") (pinfunction "NC_L9") (pintype "passive+no_connect"))
    )
  )
)
